# LPCB225_-_CLOCK.net
KiCad netlist of a schematic drawn in Altium Designer
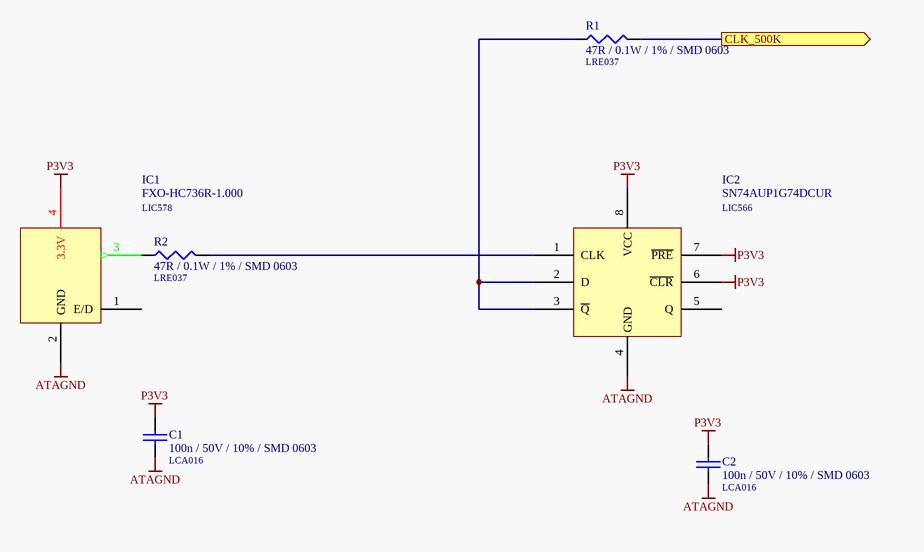
[diagram p0: LPCB225 - CLOCK.SchDoc]

(export (version "E")
  (design (tool "Eeschema 10.0.6"))
  (components
    (comp (ref "C1")
      (value "100n / 50V / 10% / SMD 0603")
      (footprint "LFP011__CC1608-0603-IPC7351_B")
      (description "Capacitor, Ceramic Chip, 100nF (0.1uF), 50V, 5%, SMD 0603 [LCA016]")
      (fields (field (name "LDL_NUMBER") "LCA016"))
      (libsource (lib "LDL_Capacitors") (part "100n / 50V / 10% / SMD 0603"))
    )
    (comp (ref "C2")
      (value "100n / 50V / 10% / SMD 0603")
      (footprint "LFP011__CC1608-0603-IPC7351_B")
      (description "Capacitor, Ceramic Chip, 100nF (0.1uF), 50V, 5%, SMD 0603 [LCA016]")
      (fields (field (name "LDL_NUMBER") "LCA016"))
      (libsource (lib "LDL_Capacitors") (part "100n / 50V / 10% / SMD 0603"))
    )
    (comp (ref "IC1")
      (value "FXO-HC736R-1.000")
      (footprint "LFP132__SMO-190")
      (description "IC, Oscillator Module, 1MHz, 3.3V, SMD [LIC578]")
      (fields (field (name "LDL_NUMBER") "LIC578"))
      (libsource (lib "LDL_Semiconductors") (part "FXO-HC736R-1.000"))
    )
    (comp (ref "IC2")
      (value "SN74AUP1G74DCUR")
      (footprint "LFP052__DCU-S-PDSO-G8")
      (description "IC, Flip Flop, SMD SOP8 [LIC566]")
      (fields (field (name "LDL_NUMBER") "LIC566"))
      (libsource (lib "LDL_Semiconductors") (part "SN74AUP1G74DCUR"))
    )
    (comp (ref "R1")
      (value "47R / 0.1W / 1% / SMD 0603")
      (footprint "LFP020__CR1608-0603-IPC7351_B")
      (description "Resistor, Ceramic Chip, 47R, 0.1W, 1%, SMD 0603 [LRE037]")
      (fields (field (name "LDL_NUMBER") "LRE037"))
      (libsource (lib "LDL_Resistors") (part "47R / 0.1W / 1% / SMD 0603"))
    )
    (comp (ref "R2")
      (value "47R / 0.1W / 1% / SMD 0603")
      (footprint "LFP020__CR1608-0603-IPC7351_B")
      (description "Resistor, Ceramic Chip, 47R, 0.1W, 1%, SMD 0603 [LRE037]")
      (fields (field (name "LDL_NUMBER") "LRE037"))
      (libsource (lib "LDL_Resistors") (part "47R / 0.1W / 1% / SMD 0603"))
    )
  )
  (nets
    (net (code "1") (name "/CLK_500K") (class "Default") (node (ref "R1") (pin "2") (pintype "passive")))
    (net (code "2") (name "ATAGND") (class "Default")
      (node (ref "C1") (pin "2") (pintype "passive"))
      (node (ref "C2") (pin "2") (pintype "passive"))
      (node (ref "IC1") (pin "2") (pinfunction "GND_2") (pintype "power_in"))
      (node (ref "IC2") (pin "4") (pinfunction "GND_4") (pintype "passive"))
    )
    (net (code "3") (name "Net-(IC1-OUT)") (class "Default")
      (node (ref "IC1") (pin "3") (pinfunction "OUT_3") (pintype "output"))
      (node (ref "R2") (pin "1") (pintype "passive"))
    )
    (net (code "4") (name "Net-(IC2-CLK)") (class "Default")
      (node (ref "IC2") (pin "1") (pinfunction "CLK_1") (pintype "passive"))
      (node (ref "R2") (pin "2") (pintype "passive"))
    )
    (net (code "5") (name "Net-(IC2-D)") (class "Default")
      (node (ref "IC2") (pin "2") (pinfunction "D_2") (pintype "passive"))
      (node (ref "IC2") (pin "3") (pinfunction "~{Q}_3") (pintype "passive"))
      (node (ref "R1") (pin "1") (pintype "passive"))
    )
    (net (code "6") (name "P3V3") (class "Default")
      (node (ref "C1") (pin "1") (pintype "passive"))
      (node (ref "C2") (pin "1") (pintype "passive"))
      (node (ref "IC1") (pin "4") (pinfunction "3.3V_4") (pintype "power_in"))
      (node (ref "IC2") (pin "6") (pinfunction "~{CLR}_6") (pintype "passive"))
      (node (ref "IC2") (pin "7") (pinfunction "~{PRE}_7") (pintype "passive"))
      (node (ref "IC2") (pin "8") (pinfunction "VCC_8") (pintype "passive"))
    )
    (net (code "7") (name "unconnected-(IC1-E{slash}D-Pad1)") (class "Default")
      (node (ref "IC1") (pin "1") (pinfunction "E/D_1") (pintype "passive"))
    )
    (net (code "8") (name "unconnected-(IC2-Q-Pad5)") (class "Default")
      (node (ref "IC2") (pin "5") (pinfunction "Q_5") (pintype "passive"))
    )
  )
)
